# power-v0v75.net
KiCad netlist of a schematic drawn in Altium Designer
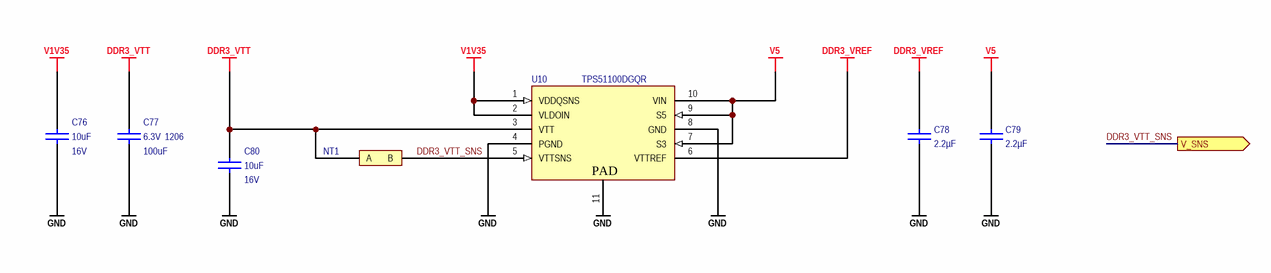
[diagram p0: power-v0v75.SchDoc]

(export (version "E")
  (design (tool "Eeschema 10.0.6"))
  (components
    (comp (ref "C76")
      (value "10uF")
      (footprint "CAPC1608X90N")
      (description "Ceramic Capacitor 10uF +/-20% 16V X5R 0603")
      (fields
        (field (name "MANUFACTURER") "Taiyo Yuden")
        (field (name "VOLTAGE") "16V")
        (field (name "Comment") "CAP 10UF 0603")
      )
      (libsource (lib "generic") (part "CAP"))
    )
    (comp (ref "C77")
      (value "100uF")
      (footprint "generic:CAPC3216X180L55N")
      (description "Ceramic Capacitor 100uF +/-20% 6.3V X5R 1206")
      (fields
        (field (name "MANUFACTURER") "Murata Electronics")
        (field (name "VOLTAGE") "6.3V")
        (field (name "PCB PACKAGE") "1206")
        (field (name "Comment") "GRM31CR60J107ME39K")
      )
      (libsource (lib "generic") (part "CAP"))
    )
    (comp (ref "C78")
      (value "2.2µF")
      (footprint "CAPC1608X90N")
      (description "CAP CER 2.2UF 10V 10% X7R 0603")
      (fields (field (name "MANUFACTURER") "Murata Electronics") (field (name "TOLERANCE") "±10%"))
      (libsource (lib "murata") (part "GRM188R71A225KE15D"))
    )
    (comp (ref "C79")
      (value "2.2µF")
      (footprint "CAPC1608X90N")
      (description "CAP CER 2.2UF 10V 10% X7R 0603")
      (fields (field (name "MANUFACTURER") "Murata Electronics") (field (name "TOLERANCE") "±10%"))
      (libsource (lib "murata") (part "GRM188R71A225KE15D"))
    )
    (comp (ref "C80")
      (value "10uF")
      (footprint "CAPC1608X90N")
      (description "Ceramic Capacitor 10uF +/-20% 16V X5R 0603")
      (fields
        (field (name "MANUFACTURER") "Taiyo Yuden")
        (field (name "VOLTAGE") "16V")
        (field (name "Comment") "EMK107BBJ106MA-T")
      )
      (libsource (lib "generic") (part "CAP"))
    )
    (comp (ref "NT1")
      (value "NET_TIE")
      (footprint "NET_TIE")
      (libsource (lib "copper_suicide") (part "NET_TIE"))
    )
    (comp (ref "U10")
      (value "TPS51100DGQR")
      (footprint "SOP11P50_300X490X110L55X22T157X188N")
      (description "IC Voltage Reg DDR1/2/3 VTT")
      (fields (field (name "MANUFACTURER") "Texas Instruments"))
      (libsource (lib "Kron Library Rev 3") (part "TPS51100DGQR"))
    )
  )
  (nets
    (net (code "1") (name "/DDR3_VTT_SNS") (class "Default")
      (node (ref "NT1") (pin "B") (pinfunction "B_B") (pintype "passive"))
      (node (ref "U10") (pin "5") (pinfunction "VTTSNS_5") (pintype "input"))
    )
    (net (code "2") (name "DDR3_VREF") (class "Default")
      (node (ref "C78") (pin "2") (pinfunction "2_2") (pintype "passive"))
      (node (ref "U10") (pin "6") (pinfunction "VTTREF_6") (pintype "power_in"))
    )
    (net (code "3") (name "DDR3_VTT") (class "Default")
      (node (ref "C77") (pin "1") (pinfunction "1_1") (pintype "passive"))
      (node (ref "C80") (pin "2") (pinfunction "2_2") (pintype "passive"))
      (node (ref "NT1") (pin "A") (pinfunction "A_A") (pintype "passive"))
      (node (ref "U10") (pin "3") (pinfunction "VTT_3") (pintype "power_in"))
    )
    (net (code "4") (name "GND") (class "Default")
      (node (ref "C76") (pin "1") (pinfunction "1_1") (pintype "passive"))
      (node (ref "C77") (pin "2") (pinfunction "2_2") (pintype "passive"))
      (node (ref "C78") (pin "1") (pinfunction "1_1") (pintype "passive"))
      (node (ref "C79") (pin "1") (pinfunction "1_1") (pintype "passive"))
      (node (ref "C80") (pin "1") (pinfunction "1_1") (pintype "passive"))
      (node (ref "U10") (pin "11") (pinfunction "PAD_11") (pintype "passive"))
      (node (ref "U10") (pin "4") (pinfunction "PGND_4") (pintype "power_in"))
      (node (ref "U10") (pin "8") (pinfunction "GND_8") (pintype "power_in"))
    )
    (net (code "5") (name "V1V35") (class "Default")
      (node (ref "C76") (pin "2") (pinfunction "2_2") (pintype "passive"))
      (node (ref "U10") (pin "1") (pinfunction "VDDQSNS_1") (pintype "input"))
      (node (ref "U10") (pin "2") (pinfunction "VLDOIN_2") (pintype "power_in"))
    )
    (net (code "6") (name "V5") (class "Default")
      (node (ref "C79") (pin "2") (pinfunction "2_2") (pintype "passive"))
      (node (ref "U10") (pin "10") (pinfunction "VIN_10") (pintype "power_in"))
      (node (ref "U10") (pin "7") (pinfunction "S3_7") (pintype "input"))
      (node (ref "U10") (pin "9") (pinfunction "S5_9") (pintype "input"))
    )
  )
)
